# MINI_SAM_D51_001.net
KiCad netlist of a schematic drawn in EAGLE
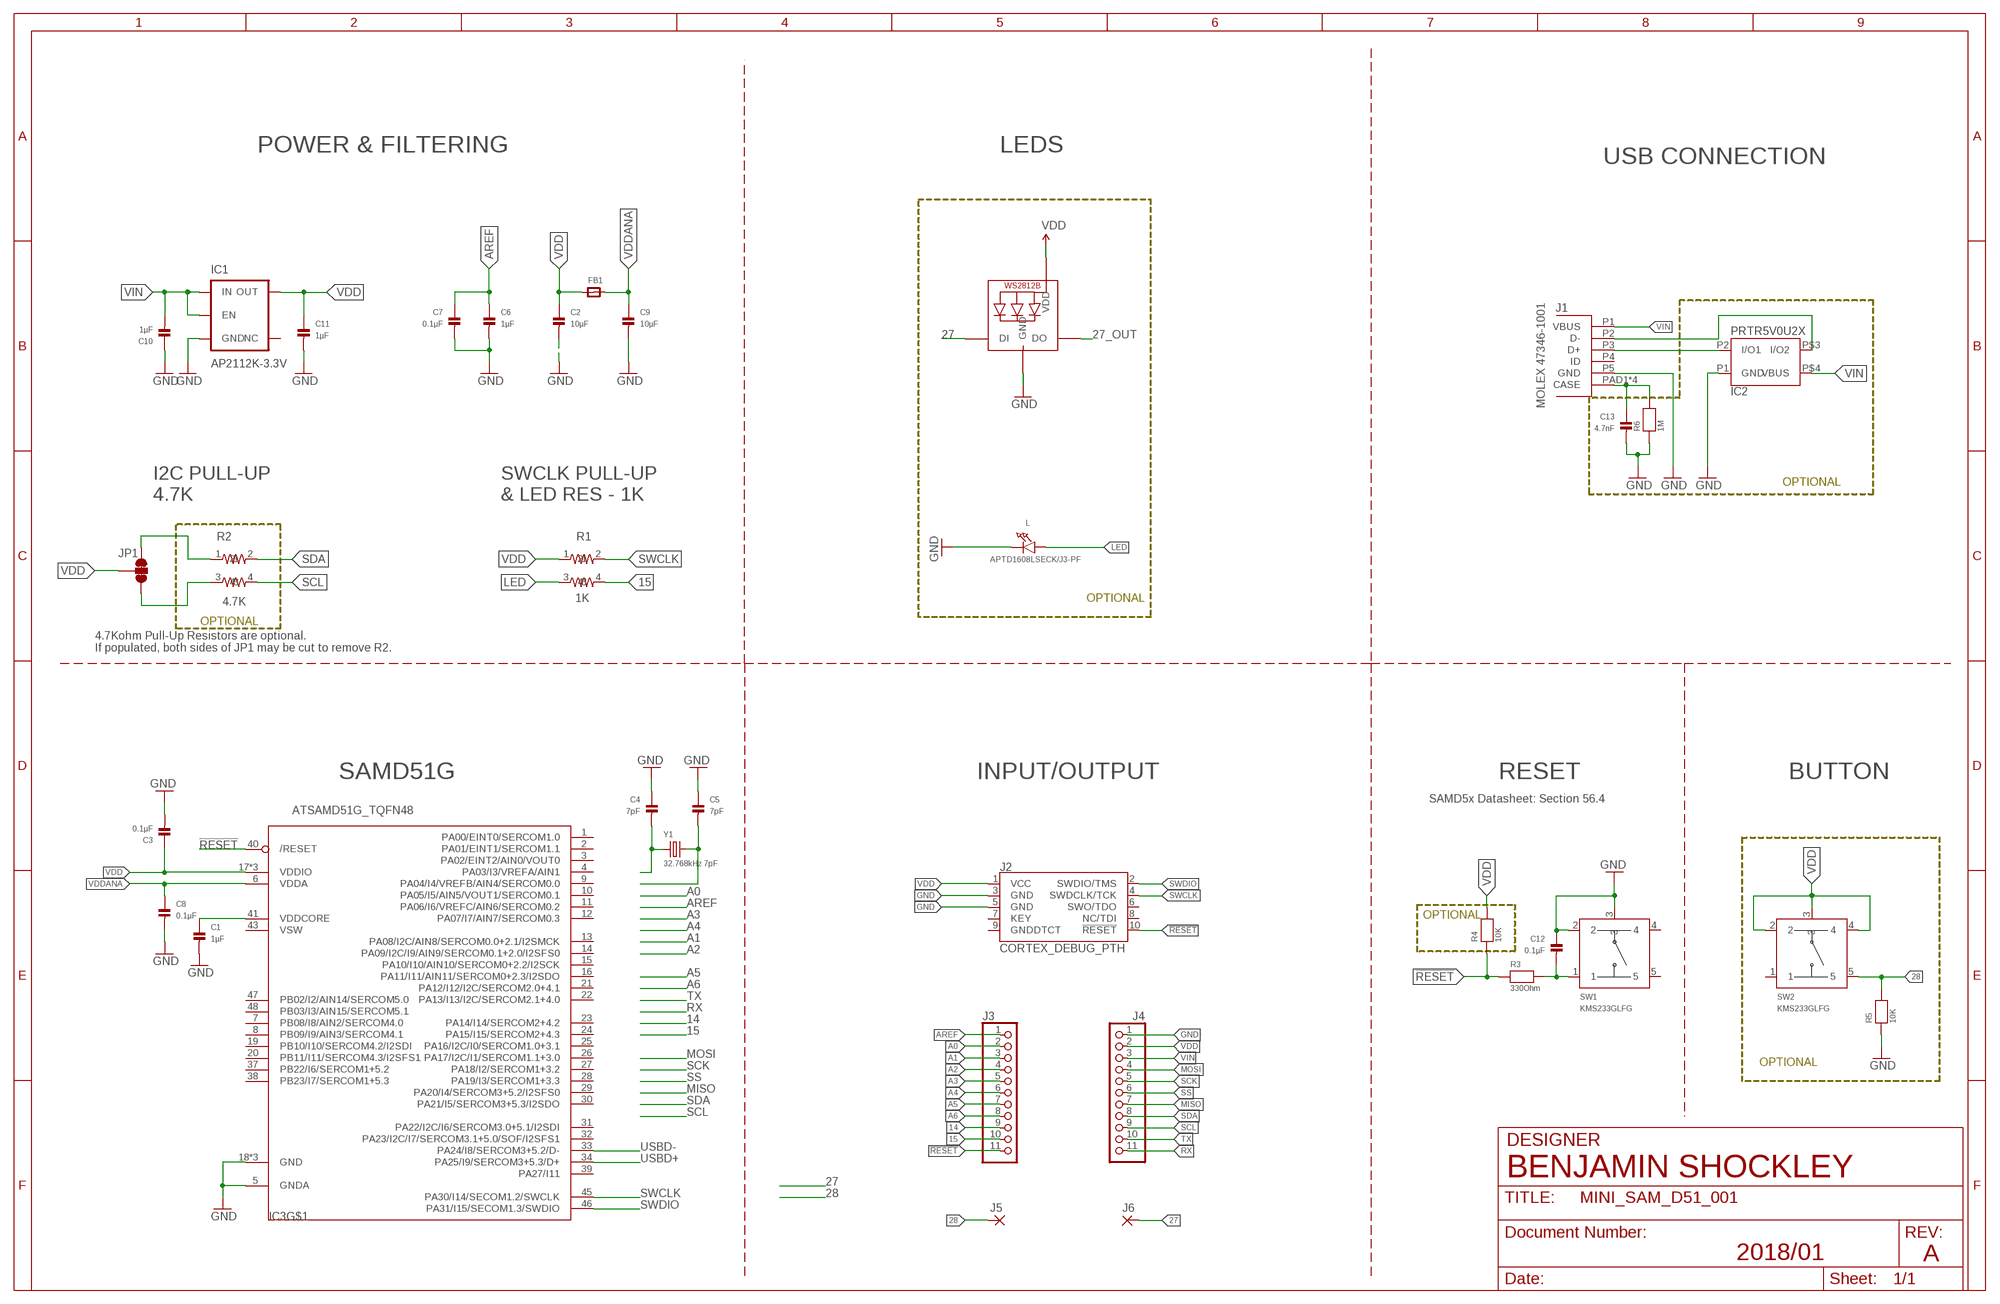
[diagram p0: schematic, sheet 1]

(export (version "E")
  (design (tool "Eeschema 10.0.6"))
  (components
    (comp (ref "C1")
      (value "1µF")
      (footprint "eagle-import:_0805MP")
      (libsource (lib "eagle-import") (part "CAP_CERAMIC_0805MP"))
    )
    (comp (ref "C2")
      (value "10µF")
      (footprint "eagle-import:_0805MP")
      (libsource (lib "eagle-import") (part "CAP_CERAMIC_0805MP"))
    )
    (comp (ref "C3")
      (value "0.1µF")
      (footprint "eagle-import:_0805MP")
      (libsource (lib "eagle-import") (part "CAP_CERAMIC_0805MP"))
    )
    (comp (ref "C4")
      (value "7pF")
      (footprint "eagle-import:_0805MP")
      (libsource (lib "eagle-import") (part "CAP_CERAMIC_0805MP"))
    )
    (comp (ref "C5")
      (value "7pF")
      (footprint "eagle-import:_0805MP")
      (libsource (lib "eagle-import") (part "CAP_CERAMIC_0805MP"))
    )
    (comp (ref "C6")
      (value "1µF")
      (footprint "eagle-import:_0805MP")
      (libsource (lib "eagle-import") (part "CAP_CERAMIC_0805MP"))
    )
    (comp (ref "C7")
      (value "0.1µF")
      (footprint "eagle-import:_0805MP")
      (libsource (lib "eagle-import") (part "CAP_CERAMIC_0805MP"))
    )
    (comp (ref "C8")
      (value "0.1µF")
      (footprint "eagle-import:_0805MP")
      (libsource (lib "eagle-import") (part "CAP_CERAMIC_0805MP"))
    )
    (comp (ref "C9")
      (value "10µF")
      (footprint "eagle-import:_0805MP")
      (libsource (lib "eagle-import") (part "CAP_CERAMIC_0805MP"))
    )
    (comp (ref "C10")
      (value "1µF")
      (footprint "eagle-import:_0805MP")
      (libsource (lib "eagle-import") (part "CAP_CERAMIC_0805MP"))
    )
    (comp (ref "C11")
      (value "1µF")
      (footprint "eagle-import:_0805MP")
      (libsource (lib "eagle-import") (part "CAP_CERAMIC_0805MP"))
    )
    (comp (ref "C12")
      (value "0.1µF")
      (footprint "eagle-import:_0805MP")
      (libsource (lib "eagle-import") (part "CAP_CERAMIC_0805MP"))
    )
    (comp (ref "C13")
      (value "4.7nF")
      (footprint "eagle-import:_0805MP")
      (libsource (lib "eagle-import") (part "CAP_CERAMIC_0805MP"))
    )
    (comp (ref "FB1")
      (value "FERRITE_0805MP")
      (footprint "eagle-import:_0805MP")
      (libsource (lib "eagle-import") (part "FERRITE_0805MP"))
    )
    (comp (ref "IC1")
      (value "AP2112K-3.3V")
      (footprint "eagle-import:SOT23-5")
      (libsource (lib "eagle-import") (part "V_REG_AP2112K-3.3V"))
    )
    (comp (ref "IC2")
      (value "PRTR5V0U2X")
      (footprint "eagle-import:SOT143B_REFLOW")
      (libsource (lib "eagle-import") (part "PRTR5V0U2X"))
    )
    (comp (ref "IC3")
      (value "ATSAMD51G_TQFN48")
      (footprint "eagle-import:TQFN48_7MM")
      (libsource (lib "eagle-import") (part "ATSAMD51G_TQFN48"))
    )
    (comp (ref "J1")
      (value "MOLEX_47346-100147346")
      (footprint "eagle-import:MOLEX_47346-1001")
      (libsource (lib "eagle-import") (part "MOLEX_47346-100147346"))
    )
    (comp (ref "J2")
      (value "CORTEX_DEBUG_PTH")
      (footprint "eagle-import:2X5-PTH-1.27MM")
      (libsource (lib "eagle-import") (part "CORTEX_DEBUG_PTH"))
    )
    (comp (ref "J3")
      (value "PINHD-1X111X11_SMT")
      (footprint "eagle-import:1X11_SMT")
      (libsource (lib "eagle-import") (part "PINHD-1X111X11_SMT"))
    )
    (comp (ref "J4")
      (value "PINHD-1X111X11_SMT")
      (footprint "eagle-import:1X11_SMT")
      (libsource (lib "eagle-import") (part "PINHD-1X111X11_SMT"))
    )
    (comp (ref "J5")
      (value "FR11_PAD2MMX1MM")
      (footprint "eagle-import:SMD2MMX1MM")
      (libsource (lib "eagle-import") (part "FR11_PAD2MMX1MM"))
    )
    (comp (ref "J6")
      (value "FR11_PAD2MMX1MM")
      (footprint "eagle-import:SMD2MMX1MM")
      (libsource (lib "eagle-import") (part "FR11_PAD2MMX1MM"))
    )
    (comp (ref "JP1")
      (value "JUMPER-SMT_3_2-NC_TRACE_NO-SILK")
      (footprint "eagle-import:SMT-JUMPER_3_2-NC_TRACE_NO-SILK")
      (libsource (lib "eagle-import") (part "JUMPER-SMT_3_2-NC_TRACE_NO-SILK"))
    )
    (comp (ref "L")
      (value "APTD1608LSECK/J3-PF")
      (footprint "eagle-import:CHIPLED_0603_NOOUTLINE")
      (libsource (lib "eagle-import") (part "LED0603_NOOUTLINE"))
    )
    (comp (ref "R1")
      (value "1K")
      (footprint "eagle-import:RESISTOR_ARRAY_0606")
      (libsource (lib "eagle-import") (part "RESISTOR_ARRAY_2"))
    )
    (comp (ref "R2")
      (value "4.7K")
      (footprint "eagle-import:RESISTOR_ARRAY_0606")
      (libsource (lib "eagle-import") (part "RESISTOR_ARRAY_2"))
    )
    (comp (ref "R3")
      (value "330Ohm")
      (footprint "eagle-import:_0805MP")
      (libsource (lib "eagle-import") (part "RESISTOR_0805MP"))
    )
    (comp (ref "R4")
      (value "10K")
      (footprint "eagle-import:_0805MP")
      (libsource (lib "eagle-import") (part "RESISTOR_0805MP"))
    )
    (comp (ref "R5")
      (value "10K")
      (footprint "eagle-import:_0805MP")
      (libsource (lib "eagle-import") (part "RESISTOR_0805MP"))
    )
    (comp (ref "R6")
      (value "1M")
      (footprint "eagle-import:_0805MP")
      (libsource (lib "eagle-import") (part "RESISTOR_0805MP"))
    )
    (comp (ref "RGB")
      (value "WS2812B3535")
      (footprint "eagle-import:LED3535")
      (libsource (lib "eagle-import") (part "WS2812B3535"))
    )
    (comp (ref "SW1")
      (value "KMS233GLFG")
      (footprint "eagle-import:KMS_SWITCH")
      (libsource (lib "eagle-import") (part "KMS_SWITCHKMS"))
    )
    (comp (ref "SW2")
      (value "KMS233GLFG")
      (footprint "eagle-import:KMS_SWITCH")
      (libsource (lib "eagle-import") (part "KMS_SWITCHKMS"))
    )
    (comp (ref "Y1")
      (value "32.768kHz 7pF")
      (footprint "eagle-import:_0805MP")
      (libsource (lib "eagle-import") (part "CRYSTAL0805PACKAGE"))
    )
  )
  (nets
    (net (code "1") (name "/27_OUT") (class "Default")
      (node (ref "RGB") (pin "3") (pinfunction "DO_3") (pintype "output"))
    )
    (net (code "2") (name "/USBD+") (class "Default")
      (node (ref "IC2") (pin "P2") (pinfunction "I/O1_P2") (pintype "bidirectional"))
      (node (ref "IC3") (pin "34") (pinfunction "PA25/I9/SERCOM3+5.3/D+_34") (pintype "bidirectional"))
      (node (ref "J1") (pin "P3") (pinfunction "D+_P3") (pintype "bidirectional"))
    )
    (net (code "3") (name "/USBD-") (class "Default")
      (node (ref "IC2") (pin "P$3") (pinfunction "I/O2_P$3") (pintype "bidirectional"))
      (node (ref "IC3") (pin "33") (pinfunction "PA24/I8/SERCOM3+5.2/D-_33") (pintype "bidirectional"))
      (node (ref "J1") (pin "P2") (pinfunction "D-_P2") (pintype "bidirectional"))
    )
    (net (code "4") (name "/VSW") (class "Default")
      (node (ref "IC3") (pin "43") (pinfunction "VSW_43") (pintype "power_in"))
    )
    (net (code "5") (name "/~{RESET}") (class "Default")
      (node (ref "IC3") (pin "40") (pinfunction "/RESET_40") (pintype "bidirectional"))
      (node (ref "J2") (pin "10") (pinfunction "~{RESET}_10") (pintype "bidirectional"))
      (node (ref "J3") (pin "11") (pinfunction "11_11") (pintype "passive"))
      (node (ref "R3") (pin "1") (pinfunction "1_1") (pintype "passive"))
      (node (ref "R4") (pin "1") (pinfunction "1_1") (pintype "passive"))
    )
    (net (code "6") (name "14") (class "Default")
      (node (ref "J3") (pin "9") (pinfunction "9_9") (pintype "passive"))
    )
    (net (code "7") (name "15") (class "Default")
      (node (ref "J3") (pin "10") (pinfunction "10_10") (pintype "passive"))
      (node (ref "R1") (pin "4") (pinfunction "4_4") (pintype "passive"))
    )
    (net (code "8") (name "27") (class "Default")
      (node (ref "J6") (pin "P$1") (pinfunction "P_P$1") (pintype "passive"))
      (node (ref "RGB") (pin "1") (pinfunction "DI_1") (pintype "input"))
    )
    (net (code "9") (name "28") (class "Default")
      (node (ref "J5") (pin "P$1") (pinfunction "P_P$1") (pintype "passive"))
      (node (ref "R5") (pin "2") (pinfunction "2_2") (pintype "passive"))
      (node (ref "SW2") (pin "5") (pinfunction "5_5") (pintype "bidirectional"))
    )
    (net (code "10") (name "A0") (class "Default")
      (node (ref "J3") (pin "2") (pinfunction "2_2") (pintype "passive"))
    )
    (net (code "11") (name "A1") (class "Default")
      (node (ref "J3") (pin "3") (pinfunction "3_3") (pintype "passive"))
    )
    (net (code "12") (name "A2") (class "Default")
      (node (ref "J3") (pin "4") (pinfunction "4_4") (pintype "passive"))
    )
    (net (code "13") (name "A3") (class "Default")
      (node (ref "J3") (pin "5") (pinfunction "5_5") (pintype "passive"))
    )
    (net (code "14") (name "A4") (class "Default")
      (node (ref "J3") (pin "6") (pinfunction "6_6") (pintype "passive"))
    )
    (net (code "15") (name "A5") (class "Default")
      (node (ref "J3") (pin "7") (pinfunction "7_7") (pintype "passive"))
    )
    (net (code "16") (name "A6") (class "Default")
      (node (ref "J3") (pin "8") (pinfunction "8_8") (pintype "passive"))
    )
    (net (code "17") (name "AREF") (class "Default")
      (node (ref "C6") (pin "1") (pinfunction "P$1_1") (pintype "passive"))
      (node (ref "C7") (pin "1") (pinfunction "P$1_1") (pintype "passive"))
      (node (ref "J3") (pin "1") (pinfunction "1_1") (pintype "passive"))
    )
    (net (code "18") (name "GND") (class "Default")
      (node (ref "C1") (pin "2") (pinfunction "P$2_2") (pintype "passive"))
      (node (ref "C10") (pin "1") (pinfunction "P$1_1") (pintype "passive"))
      (node (ref "C11") (pin "2") (pinfunction "P$2_2") (pintype "passive"))
      (node (ref "C12") (pin "1") (pinfunction "P$1_1") (pintype "passive"))
      (node (ref "C13") (pin "2") (pinfunction "P$2_2") (pintype "passive"))
      (node (ref "C2") (pin "2") (pinfunction "P$2_2") (pintype "passive"))
      (node (ref "C3") (pin "2") (pinfunction "P$2_2") (pintype "passive"))
      (node (ref "C4") (pin "1") (pinfunction "P$1_1") (pintype "passive"))
      (node (ref "C5") (pin "1") (pinfunction "P$1_1") (pintype "passive"))
      (node (ref "C6") (pin "2") (pinfunction "P$2_2") (pintype "passive"))
      (node (ref "C7") (pin "2") (pinfunction "P$2_2") (pintype "passive"))
      (node (ref "C8") (pin "2") (pinfunction "P$2_2") (pintype "passive"))
      (node (ref "C9") (pin "2") (pinfunction "P$2_2") (pintype "passive"))
      (node (ref "IC1") (pin "2") (pinfunction "GND_2") (pintype "input"))
      (node (ref "IC2") (pin "P1") (pinfunction "GND_P1") (pintype "bidirectional"))
      (node (ref "IC3") (pin "18") (pinfunction "GND_18") (pintype "power_in"))
      (node (ref "IC3") (pin "35") (pinfunction "GND_35") (pintype "power_in"))
      (node (ref "IC3") (pin "42") (pinfunction "GND_42") (pintype "power_in"))
      (node (ref "IC3") (pin "5") (pinfunction "GNDA_5") (pintype "power_in"))
      (node (ref "J1") (pin "P5") (pinfunction "GND_P5") (pintype "power_in"))
      (node (ref "J2") (pin "3") (pinfunction "GND_3") (pintype "bidirectional"))
      (node (ref "J2") (pin "5") (pinfunction "GND_5") (pintype "bidirectional"))
      (node (ref "J4") (pin "1") (pinfunction "1_1") (pintype "passive"))
      (node (ref "L") (pin "C") (pinfunction "C_C") (pintype "passive"))
      (node (ref "R5") (pin "1") (pinfunction "1_1") (pintype "passive"))
      (node (ref "R6") (pin "1") (pinfunction "1_1") (pintype "passive"))
      (node (ref "RGB") (pin "4") (pinfunction "GND_4") (pintype "power_in"))
      (node (ref "SW1") (pin "2") (pinfunction "2_2") (pintype "bidirectional"))
      (node (ref "SW1") (pin "3") (pinfunction "3_3") (pintype "bidirectional"))
    )
    (net (code "19") (name "LED") (class "Default")
      (node (ref "L") (pin "A") (pinfunction "A_A") (pintype "passive"))
      (node (ref "R1") (pin "3") (pinfunction "3_3") (pintype "passive"))
    )
    (net (code "20") (name "MISO") (class "Default")
      (node (ref "J4") (pin "7") (pinfunction "7_7") (pintype "passive"))
    )
    (net (code "21") (name "MOSI") (class "Default")
      (node (ref "J4") (pin "4") (pinfunction "4_4") (pintype "passive"))
    )
    (net (code "22") (name "Net-(C1-P$1)") (class "Default")
      (node (ref "C1") (pin "1") (pinfunction "P$1_1") (pintype "passive"))
      (node (ref "IC3") (pin "41") (pinfunction "VDDCORE_41") (pintype "power_in"))
    )
    (net (code "23") (name "Net-(C4-P$2)") (class "Default")
      (node (ref "C4") (pin "2") (pinfunction "P$2_2") (pintype "passive"))
      (node (ref "Y1") (pin "1") (pinfunction "1_1") (pintype "passive"))
    )
    (net (code "24") (name "Net-(C5-P$2)") (class "Default")
      (node (ref "C5") (pin "2") (pinfunction "P$2_2") (pintype "passive"))
      (node (ref "Y1") (pin "2") (pinfunction "2_2") (pintype "passive"))
    )
    (net (code "25") (name "Net-(C12-P$2)") (class "Default")
      (node (ref "C12") (pin "2") (pinfunction "P$2_2") (pintype "passive"))
      (node (ref "R3") (pin "2") (pinfunction "2_2") (pintype "passive"))
      (node (ref "SW1") (pin "1") (pinfunction "1_1") (pintype "bidirectional"))
    )
    (net (code "26") (name "Net-(C13-P$1)") (class "Default")
      (node (ref "C13") (pin "1") (pinfunction "P$1_1") (pintype "passive"))
      (node (ref "J1") (pin "PAD1") (pinfunction "CASE_PAD1") (pintype "bidirectional"))
      (node (ref "J1") (pin "PAD2") (pinfunction "CASE_PAD2") (pintype "bidirectional"))
      (node (ref "J1") (pin "PAD3") (pinfunction "CASE_PAD3") (pintype "bidirectional"))
      (node (ref "J1") (pin "PAD4") (pinfunction "CASE_PAD4") (pintype "bidirectional"))
      (node (ref "R6") (pin "2") (pinfunction "2_2") (pintype "passive"))
    )
    (net (code "27") (name "Net-(JP1-Pad1)") (class "Default")
      (node (ref "JP1") (pin "1") (pinfunction "1_1") (pintype "passive"))
      (node (ref "R2") (pin "1") (pinfunction "1_1") (pintype "passive"))
    )
    (net (code "28") (name "Net-(JP1-Pad3)") (class "Default")
      (node (ref "JP1") (pin "3") (pinfunction "3_3") (pintype "passive"))
      (node (ref "R2") (pin "3") (pinfunction "3_3") (pintype "passive"))
    )
    (net (code "29") (name "RX") (class "Default")
      (node (ref "J4") (pin "11") (pinfunction "11_11") (pintype "passive"))
    )
    (net (code "30") (name "SCK") (class "Default")
      (node (ref "J4") (pin "5") (pinfunction "5_5") (pintype "passive"))
    )
    (net (code "31") (name "SCL") (class "Default")
      (node (ref "J4") (pin "9") (pinfunction "9_9") (pintype "passive"))
      (node (ref "R2") (pin "4") (pinfunction "4_4") (pintype "passive"))
    )
    (net (code "32") (name "SDA") (class "Default")
      (node (ref "J4") (pin "8") (pinfunction "8_8") (pintype "passive"))
      (node (ref "R2") (pin "2") (pinfunction "2_2") (pintype "passive"))
    )
    (net (code "33") (name "SS") (class "Default")
      (node (ref "J4") (pin "6") (pinfunction "6_6") (pintype "passive"))
    )
    (net (code "34") (name "SWCLK") (class "Default")
      (node (ref "IC3") (pin "45") (pinfunction "PA30/I14/SECOM1.2/SWCLK_45") (pintype "bidirectional"))
      (node (ref "J2") (pin "4") (pinfunction "SWDCLK/TCK_4") (pintype "bidirectional"))
      (node (ref "R1") (pin "2") (pinfunction "2_2") (pintype "passive"))
    )
    (net (code "35") (name "SWDIO") (class "Default")
      (node (ref "IC3") (pin "46") (pinfunction "PA31/I15/SECOM1.3/SWDIO_46") (pintype "bidirectional"))
      (node (ref "J2") (pin "2") (pinfunction "SWDIO/TMS_2") (pintype "bidirectional"))
    )
    (net (code "36") (name "TX") (class "Default")
      (node (ref "J4") (pin "10") (pinfunction "10_10") (pintype "passive"))
    )
    (net (code "37") (name "VDD") (class "Default")
      (node (ref "C11") (pin "1") (pinfunction "P$1_1") (pintype "passive"))
      (node (ref "C2") (pin "1") (pinfunction "P$1_1") (pintype "passive"))
      (node (ref "C3") (pin "1") (pinfunction "P$1_1") (pintype "passive"))
      (node (ref "FB1") (pin "1") (pinfunction "P$1_1") (pintype "passive"))
      (node (ref "IC1") (pin "5") (pinfunction "OUT_5") (pintype "passive"))
      (node (ref "IC3") (pin "17") (pinfunction "VDDIO_17") (pintype "power_in"))
      (node (ref "IC3") (pin "36") (pinfunction "VDDIO_36") (pintype "power_in"))
      (node (ref "IC3") (pin "44") (pinfunction "VDDIO_44") (pintype "power_in"))
      (node (ref "J2") (pin "1") (pinfunction "VCC_1") (pintype "bidirectional"))
      (node (ref "J4") (pin "2") (pinfunction "2_2") (pintype "passive"))
      (node (ref "JP1") (pin "2") (pinfunction "2_2") (pintype "passive"))
      (node (ref "R1") (pin "1") (pinfunction "1_1") (pintype "passive"))
      (node (ref "R4") (pin "2") (pinfunction "2_2") (pintype "passive"))
      (node (ref "RGB") (pin "2") (pinfunction "VDD_2") (pintype "power_in"))
      (node (ref "SW2") (pin "2") (pinfunction "2_2") (pintype "bidirectional"))
      (node (ref "SW2") (pin "3") (pinfunction "3_3") (pintype "bidirectional"))
      (node (ref "SW2") (pin "4") (pinfunction "4_4") (pintype "bidirectional"))
    )
    (net (code "38") (name "VDDANA") (class "Default")
      (node (ref "C8") (pin "1") (pinfunction "P$1_1") (pintype "passive"))
      (node (ref "C9") (pin "1") (pinfunction "P$1_1") (pintype "passive"))
      (node (ref "FB1") (pin "2") (pinfunction "P$2_2") (pintype "passive"))
      (node (ref "IC3") (pin "6") (pinfunction "VDDA_6") (pintype "power_in"))
    )
    (net (code "39") (name "VIN") (class "Default")
      (node (ref "C10") (pin "2") (pinfunction "P$2_2") (pintype "passive"))
      (node (ref "IC1") (pin "1") (pinfunction "IN_1") (pintype "input"))
      (node (ref "IC1") (pin "3") (pinfunction "EN_3") (pintype "input"))
      (node (ref "IC2") (pin "P$4") (pinfunction "VBUS_P$4") (pintype "bidirectional"))
      (node (ref "J1") (pin "P1") (pinfunction "VBUS_P1") (pintype "power_in"))
      (node (ref "J4") (pin "3") (pinfunction "3_3") (pintype "passive"))
    )
    (net (code "40") (name "unconnected-(IC1-NC-Pad4)") (class "Default")
      (node (ref "IC1") (pin "4") (pinfunction "NC_4") (pintype "input"))
    )
    (net (code "41") (name "unconnected-(IC3A-PA00{slash}EINT0{slash}SERCOM1.0-Pad1)") (class "Default")
      (node (ref "IC3") (pin "1") (pinfunction "PA00/EINT0/SERCOM1.0_1") (pintype "bidirectional"))
    )
    (net (code "42") (name "unconnected-(IC3A-PA01{slash}EINT1{slash}SERCOM1.1-Pad2)") (class "Default")
      (node (ref "IC3") (pin "2") (pinfunction "PA01/EINT1/SERCOM1.1_2") (pintype "bidirectional"))
    )
    (net (code "43") (name "unconnected-(IC3A-PA02{slash}EINT2{slash}AIN0{slash}VOUT0-Pad3)") (class "Default")
      (node (ref "IC3") (pin "3") (pinfunction "PA02/EINT2/AIN0/VOUT0_3") (pintype "bidirectional"))
    )
    (net (code "44") (name "unconnected-(IC3A-PA03{slash}I3{slash}VREFA{slash}AIN1-Pad4)") (class "Default")
      (node (ref "IC3") (pin "4") (pinfunction "PA03/I3/VREFA/AIN1_4") (pintype "bidirectional"))
    )
    (net (code "45") (name "unconnected-(IC3A-PA04{slash}I4{slash}VREFB{slash}AIN4{slash}SERCOM0.0-Pad9)") (class "Default")
      (node (ref "IC3") (pin "9") (pinfunction "PA04/I4/VREFB/AIN4/SERCOM0.0_9") (pintype "bidirectional"))
    )
    (net (code "46") (name "unconnected-(IC3A-PA05{slash}I5{slash}AIN5{slash}VOUT1{slash}SERCOM0.1-Pad10)") (class "Default")
      (node (ref "IC3") (pin "10") (pinfunction "PA05/I5/AIN5/VOUT1/SERCOM0.1_10") (pintype "bidirectional"))
    )
    (net (code "47") (name "unconnected-(IC3A-PA06{slash}I6{slash}VREFC{slash}AIN6{slash}SERCOM0.2-Pad11)") (class "Default")
      (node (ref "IC3") (pin "11") (pinfunction "PA06/I6/VREFC/AIN6/SERCOM0.2_11") (pintype "bidirectional"))
    )
    (net (code "48") (name "unconnected-(IC3A-PA07{slash}I7{slash}AIN7{slash}SERCOM0.3-Pad12)") (class "Default")
      (node (ref "IC3") (pin "12") (pinfunction "PA07/I7/AIN7/SERCOM0.3_12") (pintype "bidirectional"))
    )
    (net (code "49") (name "unconnected-(IC3A-PA08{slash}I2C{slash}AIN8{slash}SERCOM0.0+2.1{slash}I2SMCK-Pad13)") (class "Default")
      (node (ref "IC3") (pin "13") (pinfunction "PA08/I2C/AIN8/SERCOM0.0+2.1/I2SMCK_13") (pintype "bidirectional"))
    )
    (net (code "50") (name "unconnected-(IC3A-PA09{slash}I2C{slash}I9{slash}AIN9{slash}SERCOM0.1+2.0{slash}I2SFS0-Pad14)") (class "Default")
      (node (ref "IC3") (pin "14") (pinfunction "PA09/I2C/I9/AIN9/SERCOM0.1+2.0/I2SFS0_14") (pintype "bidirectional"))
    )
    (net (code "51") (name "unconnected-(IC3A-PA10{slash}I10{slash}AIN10{slash}SERCOM0+2.2{slash}I2SCK-Pad15)") (class "Default")
      (node (ref "IC3") (pin "15") (pinfunction "PA10/I10/AIN10/SERCOM0+2.2/I2SCK_15") (pintype "bidirectional"))
    )
    (net (code "52") (name "unconnected-(IC3A-PA11{slash}I11{slash}AIN11{slash}SERCOM0+2.3{slash}I2SDO-Pad16)") (class "Default")
      (node (ref "IC3") (pin "16") (pinfunction "PA11/I11/AIN11/SERCOM0+2.3/I2SDO_16") (pintype "bidirectional"))
    )
    (net (code "53") (name "unconnected-(IC3A-PA12{slash}I12{slash}I2C{slash}SERCOM2.0+4.1-Pad21)") (class "Default")
      (node (ref "IC3") (pin "21") (pinfunction "PA12/I12/I2C/SERCOM2.0+4.1_21") (pintype "bidirectional"))
    )
    (net (code "54") (name "unconnected-(IC3A-PA13{slash}I13{slash}I2C{slash}SERCOM2.1+4.0-Pad22)") (class "Default")
      (node (ref "IC3") (pin "22") (pinfunction "PA13/I13/I2C/SERCOM2.1+4.0_22") (pintype "bidirectional"))
    )
    (net (code "55") (name "unconnected-(IC3A-PA14{slash}I14{slash}SERCOM2+4.2-Pad23)") (class "Default")
      (node (ref "IC3") (pin "23") (pinfunction "PA14/I14/SERCOM2+4.2_23") (pintype "bidirectional"))
    )
    (net (code "56") (name "unconnected-(IC3A-PA15{slash}I15{slash}SERCOM2+4.3-Pad24)") (class "Default")
      (node (ref "IC3") (pin "24") (pinfunction "PA15/I15/SERCOM2+4.3_24") (pintype "bidirectional"))
    )
    (net (code "57") (name "unconnected-(IC3A-PA16{slash}I2C{slash}I0{slash}SERCOM1.0+3.1-Pad25)") (class "Default")
      (node (ref "IC3") (pin "25") (pinfunction "PA16/I2C/I0/SERCOM1.0+3.1_25") (pintype "bidirectional"))
    )
    (net (code "58") (name "unconnected-(IC3A-PA17{slash}I2C{slash}I1{slash}SERCOM1.1+3.0-Pad26)") (class "Default")
      (node (ref "IC3") (pin "26") (pinfunction "PA17/I2C/I1/SERCOM1.1+3.0_26") (pintype "bidirectional"))
    )
    (net (code "59") (name "unconnected-(IC3A-PA18{slash}I2{slash}SERCOM1+3.2-Pad27)") (class "Default")
      (node (ref "IC3") (pin "27") (pinfunction "PA18/I2/SERCOM1+3.2_27") (pintype "bidirectional"))
    )
    (net (code "60") (name "unconnected-(IC3A-PA19{slash}I3{slash}SERCOM1+3.3-Pad28)") (class "Default")
      (node (ref "IC3") (pin "28") (pinfunction "PA19/I3/SERCOM1+3.3_28") (pintype "bidirectional"))
    )
    (net (code "61") (name "unconnected-(IC3A-PA20{slash}I4{slash}SERCOM3+5.2{slash}I2SFS0-Pad29)") (class "Default")
      (node (ref "IC3") (pin "29") (pinfunction "PA20/I4/SERCOM3+5.2/I2SFS0_29") (pintype "bidirectional"))
    )
    (net (code "62") (name "unconnected-(IC3A-PA21{slash}I5{slash}SERCOM3+5.3{slash}I2SDO-Pad30)") (class "Default")
      (node (ref "IC3") (pin "30") (pinfunction "PA21/I5/SERCOM3+5.3/I2SDO_30") (pintype "bidirectional"))
    )
    (net (code "63") (name "unconnected-(IC3A-PA22{slash}I2C{slash}I6{slash}SERCOM3.0+5.1{slash}I2SDI-Pad31)") (class "Default")
      (node (ref "IC3") (pin "31") (pinfunction "PA22/I2C/I6/SERCOM3.0+5.1/I2SDI_31") (pintype "bidirectional"))
    )
    (net (code "64") (name "unconnected-(IC3A-PA23{slash}I2C{slash}I7{slash}SERCOM3.1+5.0{slash}SOF{slash}I2SFS1-Pad32)") (class "Default")
      (node (ref "IC3") (pin "32") (pinfunction "PA23/I2C/I7/SERCOM3.1+5.0/SOF/I2SFS1_32") (pintype "bidirectional"))
    )
    (net (code "65") (name "unconnected-(IC3A-PA27{slash}I11-Pad39)") (class "Default")
      (node (ref "IC3") (pin "39") (pinfunction "PA27/I11_39") (pintype "bidirectional"))
    )
    (net (code "66") (name "unconnected-(IC3A-PB02{slash}I2{slash}AIN14{slash}SERCOM5.0-Pad47)") (class "Default")
      (node (ref "IC3") (pin "47") (pinfunction "PB02/I2/AIN14/SERCOM5.0_47") (pintype "bidirectional"))
    )
    (net (code "67") (name "unconnected-(IC3A-PB03{slash}I3{slash}AIN15{slash}SERCOM5.1-Pad48)") (class "Default")
      (node (ref "IC3") (pin "48") (pinfunction "PB03/I3/AIN15/SERCOM5.1_48") (pintype "bidirectional"))
    )
    (net (code "68") (name "unconnected-(IC3A-PB08{slash}I8{slash}AIN2{slash}SERCOM4.0-Pad7)") (class "Default")
      (node (ref "IC3") (pin "7") (pinfunction "PB08/I8/AIN2/SERCOM4.0_7") (pintype "bidirectional"))
    )
    (net (code "69") (name "unconnected-(IC3A-PB09{slash}I9{slash}AIN3{slash}SERCOM4.1-Pad8)") (class "Default")
      (node (ref "IC3") (pin "8") (pinfunction "PB09/I9/AIN3/SERCOM4.1_8") (pintype "bidirectional"))
    )
    (net (code "70") (name "unconnected-(IC3A-PB10{slash}I10{slash}SERCOM4.2{slash}I2SDI-Pad19)") (class "Default")
      (node (ref "IC3") (pin "19") (pinfunction "PB10/I10/SERCOM4.2/I2SDI_19") (pintype "bidirectional"))
    )
    (net (code "71") (name "unconnected-(IC3A-PB11{slash}I11{slash}SERCOM4.3{slash}I2SFS1-Pad20)") (class "Default")
      (node (ref "IC3") (pin "20") (pinfunction "PB11/I11/SERCOM4.3/I2SFS1_20") (pintype "bidirectional"))
    )
    (net (code "72") (name "unconnected-(IC3A-PB22{slash}I6{slash}SERCOM1+5.2-Pad37)") (class "Default")
      (node (ref "IC3") (pin "37") (pinfunction "PB22/I6/SERCOM1+5.2_37") (pintype "bidirectional"))
    )
    (net (code "73") (name "unconnected-(IC3A-PB23{slash}I7{slash}SERCOM1+5.3-Pad38)") (class "Default")
      (node (ref "IC3") (pin "38") (pinfunction "PB23/I7/SERCOM1+5.3_38") (pintype "bidirectional"))
    )
    (net (code "74") (name "unconnected-(J1-ID-PadP4)") (class "Default")
      (node (ref "J1") (pin "P4") (pinfunction "ID_P4") (pintype "bidirectional"))
    )
    (net (code "75") (name "unconnected-(J2-GNDDTCT-Pad9)") (class "Default")
      (node (ref "J2") (pin "9") (pinfunction "GNDDTCT_9") (pintype "bidirectional"))
    )
    (net (code "76") (name "unconnected-(J2-KEY-Pad7)") (class "Default")
      (node (ref "J2") (pin "7") (pinfunction "KEY_7") (pintype "bidirectional"))
    )
    (net (code "77") (name "unconnected-(J2-NC{slash}TDI-Pad8)") (class "Default")
      (node (ref "J2") (pin "8") (pinfunction "NC/TDI_8") (pintype "bidirectional"))
    )
    (net (code "78") (name "unconnected-(J2-SWO{slash}TDO-Pad6)") (class "Default")
      (node (ref "J2") (pin "6") (pinfunction "SWO/TDO_6") (pintype "bidirectional"))
    )
    (net (code "79") (name "unconnected-(SW1-Pad4)") (class "Default")
      (node (ref "SW1") (pin "4") (pinfunction "4_4") (pintype "bidirectional"))
    )
    (net (code "80") (name "unconnected-(SW1-Pad5)") (class "Default")
      (node (ref "SW1") (pin "5") (pinfunction "5_5") (pintype "bidirectional"))
    )
    (net (code "81") (name "unconnected-(SW2-Pad1)") (class "Default")
      (node (ref "SW2") (pin "1") (pinfunction "1_1") (pintype "bidirectional"))
    )
  )
)
